# power_cm_v.net
KiCad netlist of a schematic drawn in Altium Designer
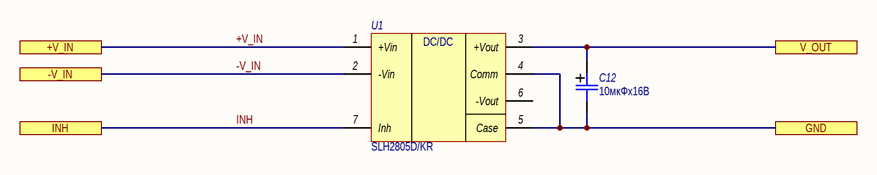
[diagram p0: power_cm_v.SchDoc]

(export (version "E")
  (design (tool "Eeschema 10.0.6"))
  (components
    (comp (ref "C12")
      (value "10мкФх16В")
      (footprint "SMD_size_B")
      (description "Polarized capacitor")
      (libsource (lib "Passive") (part "Capacitor_pol"))
    )
    (comp (ref "U1")
      (value "SLH28xx")
      (footprint "SLH28xx")
      (description "DC-DC")
      (fields (field (name "НАИМЕНОВАНИЕ") "SLH2805D/KR"))
      (libsource (lib "DC_DC") (part "SLH28xx"))
    )
  )
  (nets
    (net (code "1") (name "/+V_IN") (class "Default")
      (node (ref "U1") (pin "1") (pinfunction "+Vin_1") (pintype "open_collector"))
    )
    (net (code "2") (name "/-V_IN") (class "Default")
      (node (ref "U1") (pin "2") (pinfunction "-Vin_2") (pintype "open_collector"))
    )
    (net (code "3") (name "/GND") (class "Default")
      (node (ref "C12") (pin "2") (pinfunction "2_2") (pintype "passive"))
      (node (ref "U1") (pin "4") (pinfunction "Comm_4") (pintype "open_collector"))
      (node (ref "U1") (pin "5") (pinfunction "Case_5") (pintype "passive"))
    )
    (net (code "4") (name "/INH") (class "Default")
      (node (ref "U1") (pin "7") (pinfunction "Inh_7") (pintype "open_collector"))
    )
    (net (code "5") (name "/V_OUT") (class "Default")
      (node (ref "C12") (pin "1") (pinfunction "1_1") (pintype "passive"))
      (node (ref "U1") (pin "3") (pinfunction "+Vout_3") (pintype "open_collector"))
    )
    (net (code "6") (name "unconnected-(U1--Vout-Pad6)") (class "Default")
      (node (ref "U1") (pin "6") (pinfunction "-Vout_6") (pintype "open_collector"))
    )
  )
)
